# teensy-boom-jr.net
KiCad netlist of a schematic drawn in EAGLE
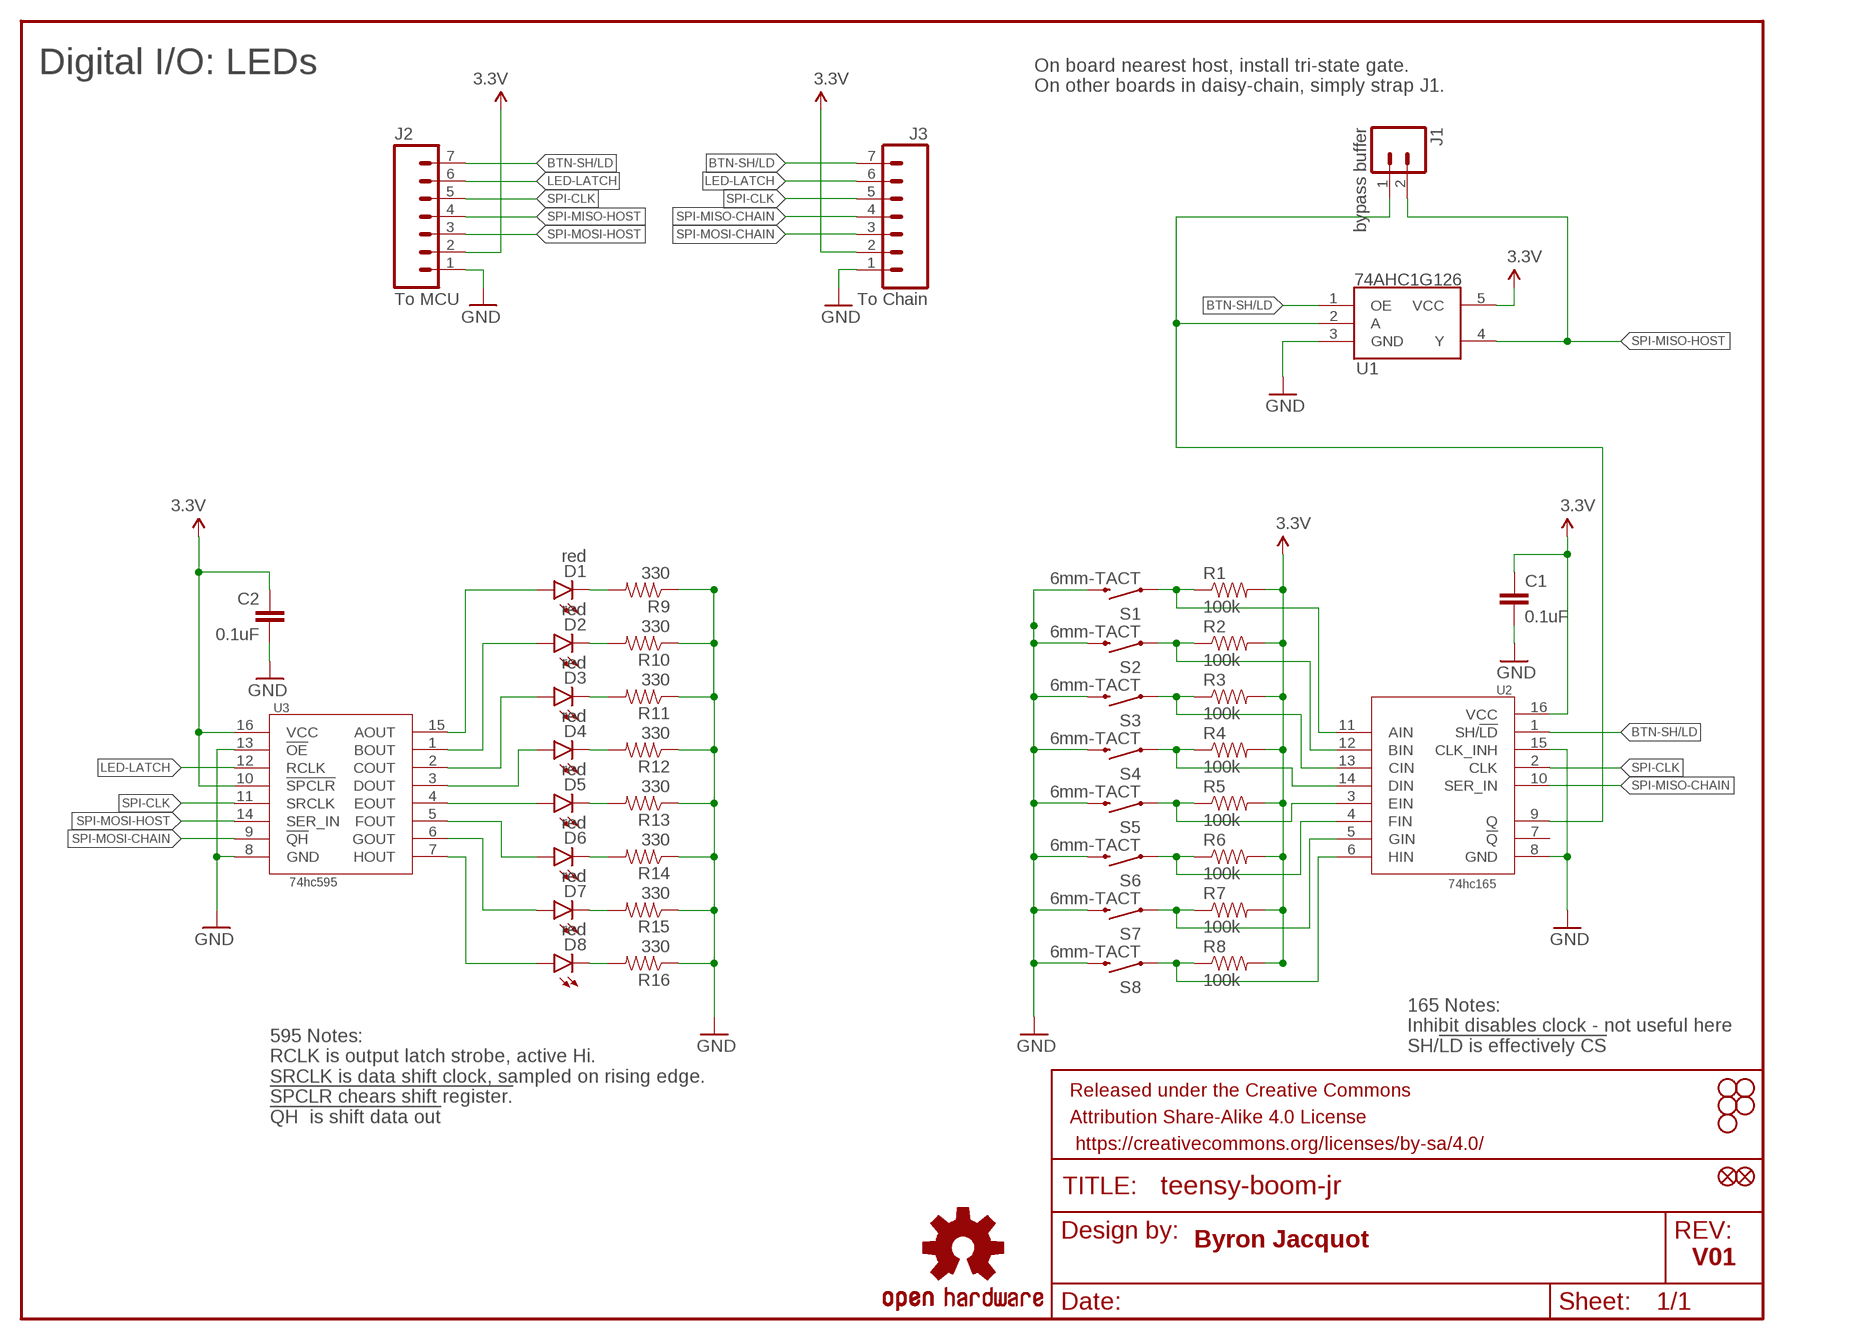
[diagram p0: schematic, sheet 1]

(export (version "E")
  (design (tool "Eeschema 10.0.6"))
  (components
    (comp (ref "C1")
      (value "0.1uF")
      (footprint "eagle-import:0603-CAP")
      (libsource (lib "eagle-import") (part "0.1UF-25V-5%(0603)"))
    )
    (comp (ref "C2")
      (value "0.1uF")
      (footprint "eagle-import:0603-CAP")
      (libsource (lib "eagle-import") (part "0.1UF-25V-5%(0603)"))
    )
    (comp (ref "D1")
      (value "red")
      (footprint "eagle-import:LED3MM-NS")
      (libsource (lib "eagle-import") (part "LED-3MM-NO_SILK"))
    )
    (comp (ref "D2")
      (value "red")
      (footprint "eagle-import:LED3MM-NS")
      (libsource (lib "eagle-import") (part "LED-3MM-NO_SILK"))
    )
    (comp (ref "D3")
      (value "red")
      (footprint "eagle-import:LED3MM-NS")
      (libsource (lib "eagle-import") (part "LED-3MM-NO_SILK"))
    )
    (comp (ref "D4")
      (value "red")
      (footprint "eagle-import:LED3MM-NS")
      (libsource (lib "eagle-import") (part "LED-3MM-NO_SILK"))
    )
    (comp (ref "D5")
      (value "red")
      (footprint "eagle-import:LED3MM-NS")
      (libsource (lib "eagle-import") (part "LED-3MM-NO_SILK"))
    )
    (comp (ref "D6")
      (value "red")
      (footprint "eagle-import:LED3MM-NS")
      (libsource (lib "eagle-import") (part "LED-3MM-NO_SILK"))
    )
    (comp (ref "D7")
      (value "red")
      (footprint "eagle-import:LED3MM-NS")
      (libsource (lib "eagle-import") (part "LED-3MM-NO_SILK"))
    )
    (comp (ref "D8")
      (value "red")
      (footprint "eagle-import:LED3MM-NS")
      (libsource (lib "eagle-import") (part "LED-3MM-NO_SILK"))
    )
    (comp (ref "FD1")
      (value "FIDUCIALUFIDUCIAL")
      (footprint "eagle-import:MICRO-FIDUCIAL")
      (libsource (lib "eagle-import") (part "FIDUCIALUFIDUCIAL"))
    )
    (comp (ref "FD2")
      (value "FIDUCIALUFIDUCIAL")
      (footprint "eagle-import:MICRO-FIDUCIAL")
      (libsource (lib "eagle-import") (part "FIDUCIALUFIDUCIAL"))
    )
    (comp (ref "FRAME1")
      (value "FRAME-LETTER")
      (footprint "eagle-import:CREATIVE_COMMONS")
      (libsource (lib "eagle-import") (part "FRAME-LETTER"))
    )
    (comp (ref "H1")
      (value "STAND-OFF")
      (footprint "eagle-import:STAND-OFF")
      (libsource (lib "eagle-import") (part "STAND-OFF"))
    )
    (comp (ref "H2")
      (value "STAND-OFF")
      (footprint "eagle-import:STAND-OFF")
      (libsource (lib "eagle-import") (part "STAND-OFF"))
    )
    (comp (ref "H3")
      (value "STAND-OFF")
      (footprint "eagle-import:STAND-OFF")
      (libsource (lib "eagle-import") (part "STAND-OFF"))
    )
    (comp (ref "H4")
      (value "STAND-OFF")
      (footprint "eagle-import:STAND-OFF")
      (libsource (lib "eagle-import") (part "STAND-OFF"))
    )
    (comp (ref "H5")
      (value "STAND-OFF")
      (footprint "eagle-import:STAND-OFF")
      (libsource (lib "eagle-import") (part "STAND-OFF"))
    )
    (comp (ref "J1")
      (value "bypass buffer")
      (footprint "eagle-import:1X02_NO_SILK")
      (libsource (lib "eagle-import") (part "M021X02_NO_SILK"))
    )
    (comp (ref "J2")
      (value "To MCU")
      (footprint "eagle-import:1X07_NO_SILK")
      (libsource (lib "eagle-import") (part "M07NO_SILK"))
    )
    (comp (ref "J3")
      (value "To Chain")
      (footprint "eagle-import:1X07_NO_SILK")
      (libsource (lib "eagle-import") (part "M07NO_SILK"))
    )
    (comp (ref "LOGO1")
      (value "OSHW-LOGOS")
      (footprint "eagle-import:OSHW-LOGO-S")
      (libsource (lib "eagle-import") (part "OSHW-LOGOS"))
    )
    (comp (ref "R1")
      (value "100k")
      (footprint "eagle-import:0805")
      (libsource (lib "eagle-import") (part "RESISTOR0805-RES"))
    )
    (comp (ref "R2")
      (value "100k")
      (footprint "eagle-import:0805")
      (libsource (lib "eagle-import") (part "RESISTOR0805-RES"))
    )
    (comp (ref "R3")
      (value "100k")
      (footprint "eagle-import:0805")
      (libsource (lib "eagle-import") (part "RESISTOR0805-RES"))
    )
    (comp (ref "R4")
      (value "100k")
      (footprint "eagle-import:0805")
      (libsource (lib "eagle-import") (part "RESISTOR0805-RES"))
    )
    (comp (ref "R5")
      (value "100k")
      (footprint "eagle-import:0805")
      (libsource (lib "eagle-import") (part "RESISTOR0805-RES"))
    )
    (comp (ref "R6")
      (value "100k")
      (footprint "eagle-import:0805")
      (libsource (lib "eagle-import") (part "RESISTOR0805-RES"))
    )
    (comp (ref "R7")
      (value "100k")
      (footprint "eagle-import:0805")
      (libsource (lib "eagle-import") (part "RESISTOR0805-RES"))
    )
    (comp (ref "R8")
      (value "100k")
      (footprint "eagle-import:0805")
      (libsource (lib "eagle-import") (part "RESISTOR0805-RES"))
    )
    (comp (ref "R9")
      (value "330")
      (footprint "eagle-import:0603-RES")
      (libsource (lib "eagle-import") (part "330OHM1/10W1%(0603)"))
    )
    (comp (ref "R10")
      (value "330")
      (footprint "eagle-import:0603-RES")
      (libsource (lib "eagle-import") (part "330OHM1/10W1%(0603)"))
    )
    (comp (ref "R11")
      (value "330")
      (footprint "eagle-import:0603-RES")
      (libsource (lib "eagle-import") (part "330OHM1/10W1%(0603)"))
    )
    (comp (ref "R12")
      (value "330")
      (footprint "eagle-import:0603-RES")
      (libsource (lib "eagle-import") (part "330OHM1/10W1%(0603)"))
    )
    (comp (ref "R13")
      (value "330")
      (footprint "eagle-import:0603-RES")
      (libsource (lib "eagle-import") (part "330OHM1/10W1%(0603)"))
    )
    (comp (ref "R14")
      (value "330")
      (footprint "eagle-import:0603-RES")
      (libsource (lib "eagle-import") (part "330OHM1/10W1%(0603)"))
    )
    (comp (ref "R15")
      (value "330")
      (footprint "eagle-import:0603-RES")
      (libsource (lib "eagle-import") (part "330OHM1/10W1%(0603)"))
    )
    (comp (ref "R16")
      (value "330")
      (footprint "eagle-import:0603-RES")
      (libsource (lib "eagle-import") (part "330OHM1/10W1%(0603)"))
    )
    (comp (ref "S1")
      (value "6mm-TACT")
      (footprint "eagle-import:TACTILE-PTH-12MM")
      (libsource (lib "eagle-import") (part "SWITCH-MOMENTARY-212MM"))
    )
    (comp (ref "S2")
      (value "6mm-TACT")
      (footprint "eagle-import:TACTILE-PTH-12MM")
      (libsource (lib "eagle-import") (part "SWITCH-MOMENTARY-212MM"))
    )
    (comp (ref "S3")
      (value "6mm-TACT")
      (footprint "eagle-import:TACTILE-PTH-12MM")
      (libsource (lib "eagle-import") (part "SWITCH-MOMENTARY-212MM"))
    )
    (comp (ref "S4")
      (value "6mm-TACT")
      (footprint "eagle-import:TACTILE-PTH-12MM")
      (libsource (lib "eagle-import") (part "SWITCH-MOMENTARY-212MM"))
    )
    (comp (ref "S5")
      (value "6mm-TACT")
      (footprint "eagle-import:TACTILE-PTH-12MM")
      (libsource (lib "eagle-import") (part "SWITCH-MOMENTARY-212MM"))
    )
    (comp (ref "S6")
      (value "6mm-TACT")
      (footprint "eagle-import:TACTILE-PTH-12MM")
      (libsource (lib "eagle-import") (part "SWITCH-MOMENTARY-212MM"))
    )
    (comp (ref "S7")
      (value "6mm-TACT")
      (footprint "eagle-import:TACTILE-PTH-12MM")
      (libsource (lib "eagle-import") (part "SWITCH-MOMENTARY-212MM"))
    )
    (comp (ref "S8")
      (value "6mm-TACT")
      (footprint "eagle-import:TACTILE-PTH-12MM")
      (libsource (lib "eagle-import") (part "SWITCH-MOMENTARY-212MM"))
    )
    (comp (ref "U1")
      (value "74AHC1G126")
      (footprint "eagle-import:SOT23-5")
      (libsource (lib "eagle-import") (part "74AHC1G126"))
    )
    (comp (ref "U2")
      (value "74hc165")
      (footprint "eagle-import:SO16")
      (libsource (lib "eagle-import") (part "74HC165"))
    )
    (comp (ref "U3")
      (value "74hc595")
      (footprint "eagle-import:SO16")
      (libsource (lib "eagle-import") (part "74HC595"))
    )
  )
  (nets
    (net (code "1") (name "3.3V") (class "Default")
      (node (ref "C1") (pin "1") (pinfunction "1_1") (pintype "passive"))
      (node (ref "C2") (pin "1") (pinfunction "1_1") (pintype "passive"))
      (node (ref "J2") (pin "2") (pinfunction "2_2") (pintype "passive"))
      (node (ref "J3") (pin "2") (pinfunction "2_2") (pintype "passive"))
      (node (ref "R1") (pin "2") (pinfunction "2_2") (pintype "passive"))
      (node (ref "R2") (pin "2") (pinfunction "2_2") (pintype "passive"))
      (node (ref "R3") (pin "2") (pinfunction "2_2") (pintype "passive"))
      (node (ref "R4") (pin "2") (pinfunction "2_2") (pintype "passive"))
      (node (ref "R5") (pin "2") (pinfunction "2_2") (pintype "passive"))
      (node (ref "R6") (pin "2") (pinfunction "2_2") (pintype "passive"))
      (node (ref "R7") (pin "2") (pinfunction "2_2") (pintype "passive"))
      (node (ref "R8") (pin "2") (pinfunction "2_2") (pintype "passive"))
      (node (ref "U1") (pin "5") (pinfunction "VCC_5") (pintype "bidirectional"))
      (node (ref "U2") (pin "16") (pinfunction "VCC_16") (pintype "bidirectional"))
      (node (ref "U3") (pin "10") (pinfunction "~{SPCLR}_10") (pintype "bidirectional"))
      (node (ref "U3") (pin "16") (pinfunction "VCC_16") (pintype "bidirectional"))
    )
    (net (code "2") (name "BTN-SH{slash}LD") (class "Default")
      (node (ref "J2") (pin "7") (pinfunction "7_7") (pintype "passive"))
      (node (ref "J3") (pin "7") (pinfunction "7_7") (pintype "passive"))
      (node (ref "U1") (pin "1") (pinfunction "OE_1") (pintype "bidirectional"))
      (node (ref "U2") (pin "1") (pinfunction "SH/~{LD}_1") (pintype "bidirectional"))
    )
    (net (code "3") (name "GND") (class "Default")
      (node (ref "C1") (pin "2") (pinfunction "2_2") (pintype "passive"))
      (node (ref "C2") (pin "2") (pinfunction "2_2") (pintype "passive"))
      (node (ref "J2") (pin "1") (pinfunction "1_1") (pintype "passive"))
      (node (ref "J3") (pin "1") (pinfunction "1_1") (pintype "passive"))
      (node (ref "R10") (pin "1") (pinfunction "1_1") (pintype "passive"))
      (node (ref "R11") (pin "1") (pinfunction "1_1") (pintype "passive"))
      (node (ref "R12") (pin "1") (pinfunction "1_1") (pintype "passive"))
      (node (ref "R13") (pin "1") (pinfunction "1_1") (pintype "passive"))
      (node (ref "R14") (pin "1") (pinfunction "1_1") (pintype "passive"))
      (node (ref "R15") (pin "1") (pinfunction "1_1") (pintype "passive"))
      (node (ref "R16") (pin "1") (pinfunction "1_1") (pintype "passive"))
      (node (ref "R9") (pin "1") (pinfunction "1_1") (pintype "passive"))
      (node (ref "S1") (pin "3") (pinfunction "2_3") (pintype "passive"))
      (node (ref "S2") (pin "3") (pinfunction "2_3") (pintype "passive"))
      (node (ref "S3") (pin "3") (pinfunction "2_3") (pintype "passive"))
      (node (ref "S4") (pin "3") (pinfunction "2_3") (pintype "passive"))
      (node (ref "S5") (pin "3") (pinfunction "2_3") (pintype "passive"))
      (node (ref "S6") (pin "3") (pinfunction "2_3") (pintype "passive"))
      (node (ref "S7") (pin "3") (pinfunction "2_3") (pintype "passive"))
      (node (ref "S8") (pin "3") (pinfunction "2_3") (pintype "passive"))
      (node (ref "U1") (pin "3") (pinfunction "GND_3") (pintype "bidirectional"))
      (node (ref "U2") (pin "15") (pinfunction "CLK_INH_15") (pintype "bidirectional"))
      (node (ref "U2") (pin "8") (pinfunction "GND_8") (pintype "bidirectional"))
      (node (ref "U3") (pin "13") (pinfunction "~{OE}_13") (pintype "bidirectional"))
      (node (ref "U3") (pin "8") (pinfunction "GND_8") (pintype "bidirectional"))
    )
    (net (code "4") (name "LED-LATCH") (class "Default")
      (node (ref "J2") (pin "6") (pinfunction "6_6") (pintype "passive"))
      (node (ref "J3") (pin "6") (pinfunction "6_6") (pintype "passive"))
      (node (ref "U3") (pin "12") (pinfunction "RCLK_12") (pintype "bidirectional"))
    )
    (net (code "5") (name "Net-(D1-C)") (class "Default")
      (node (ref "D1") (pin "K") (pinfunction "C_K") (pintype "passive"))
      (node (ref "R9") (pin "2") (pinfunction "2_2") (pintype "passive"))
    )
    (net (code "6") (name "Net-(D2-C)") (class "Default")
      (node (ref "D2") (pin "K") (pinfunction "C_K") (pintype "passive"))
      (node (ref "R10") (pin "2") (pinfunction "2_2") (pintype "passive"))
    )
    (net (code "7") (name "Net-(D3-C)") (class "Default")
      (node (ref "D3") (pin "K") (pinfunction "C_K") (pintype "passive"))
      (node (ref "R11") (pin "2") (pinfunction "2_2") (pintype "passive"))
    )
    (net (code "8") (name "Net-(D4-C)") (class "Default")
      (node (ref "D4") (pin "K") (pinfunction "C_K") (pintype "passive"))
      (node (ref "R12") (pin "2") (pinfunction "2_2") (pintype "passive"))
    )
    (net (code "9") (name "Net-(D5-C)") (class "Default")
      (node (ref "D5") (pin "K") (pinfunction "C_K") (pintype "passive"))
      (node (ref "R13") (pin "2") (pinfunction "2_2") (pintype "passive"))
    )
    (net (code "10") (name "Net-(D6-C)") (class "Default")
      (node (ref "D6") (pin "K") (pinfunction "C_K") (pintype "passive"))
      (node (ref "R14") (pin "2") (pinfunction "2_2") (pintype "passive"))
    )
    (net (code "11") (name "Net-(D7-C)") (class "Default")
      (node (ref "D7") (pin "K") (pinfunction "C_K") (pintype "passive"))
      (node (ref "R15") (pin "2") (pinfunction "2_2") (pintype "passive"))
    )
    (net (code "12") (name "Net-(D8-C)") (class "Default")
      (node (ref "D8") (pin "K") (pinfunction "C_K") (pintype "passive"))
      (node (ref "R16") (pin "2") (pinfunction "2_2") (pintype "passive"))
    )
    (net (code "13") (name "Net-(U1-A)") (class "Default")
      (node (ref "J1") (pin "1") (pinfunction "1_1") (pintype "passive"))
      (node (ref "U1") (pin "2") (pinfunction "A_2") (pintype "bidirectional"))
      (node (ref "U2") (pin "9") (pinfunction "Q_9") (pintype "bidirectional"))
    )
    (net (code "14") (name "Net-(U2-AIN)") (class "Default")
      (node (ref "R1") (pin "1") (pinfunction "1_1") (pintype "passive"))
      (node (ref "S1") (pin "1") (pinfunction "1_1") (pintype "passive"))
      (node (ref "U2") (pin "11") (pinfunction "AIN_11") (pintype "bidirectional"))
    )
    (net (code "15") (name "Net-(U2-BIN)") (class "Default")
      (node (ref "R2") (pin "1") (pinfunction "1_1") (pintype "passive"))
      (node (ref "S2") (pin "1") (pinfunction "1_1") (pintype "passive"))
      (node (ref "U2") (pin "12") (pinfunction "BIN_12") (pintype "bidirectional"))
    )
    (net (code "16") (name "Net-(U2-CIN)") (class "Default")
      (node (ref "R3") (pin "1") (pinfunction "1_1") (pintype "passive"))
      (node (ref "S3") (pin "1") (pinfunction "1_1") (pintype "passive"))
      (node (ref "U2") (pin "13") (pinfunction "CIN_13") (pintype "bidirectional"))
    )
    (net (code "17") (name "Net-(U2-DIN)") (class "Default")
      (node (ref "R4") (pin "1") (pinfunction "1_1") (pintype "passive"))
      (node (ref "S4") (pin "1") (pinfunction "1_1") (pintype "passive"))
      (node (ref "U2") (pin "14") (pinfunction "DIN_14") (pintype "bidirectional"))
    )
    (net (code "18") (name "Net-(U2-EIN)") (class "Default")
      (node (ref "R5") (pin "1") (pinfunction "1_1") (pintype "passive"))
      (node (ref "S5") (pin "1") (pinfunction "1_1") (pintype "passive"))
      (node (ref "U2") (pin "3") (pinfunction "EIN_3") (pintype "bidirectional"))
    )
    (net (code "19") (name "Net-(U2-FIN)") (class "Default")
      (node (ref "R6") (pin "1") (pinfunction "1_1") (pintype "passive"))
      (node (ref "S6") (pin "1") (pinfunction "1_1") (pintype "passive"))
      (node (ref "U2") (pin "4") (pinfunction "FIN_4") (pintype "bidirectional"))
    )
    (net (code "20") (name "Net-(U2-GIN)") (class "Default")
      (node (ref "R7") (pin "1") (pinfunction "1_1") (pintype "passive"))
      (node (ref "S7") (pin "1") (pinfunction "1_1") (pintype "passive"))
      (node (ref "U2") (pin "5") (pinfunction "GIN_5") (pintype "bidirectional"))
    )
    (net (code "21") (name "Net-(U2-HIN)") (class "Default")
      (node (ref "R8") (pin "1") (pinfunction "1_1") (pintype "passive"))
      (node (ref "S8") (pin "1") (pinfunction "1_1") (pintype "passive"))
      (node (ref "U2") (pin "6") (pinfunction "HIN_6") (pintype "bidirectional"))
    )
    (net (code "22") (name "Net-(U3-AOUT)") (class "Default")
      (node (ref "D1") (pin "A") (pinfunction "A_A") (pintype "passive"))
      (node (ref "U3") (pin "15") (pinfunction "AOUT_15") (pintype "bidirectional"))
    )
    (net (code "23") (name "Net-(U3-BOUT)") (class "Default")
      (node (ref "D2") (pin "A") (pinfunction "A_A") (pintype "passive"))
      (node (ref "U3") (pin "1") (pinfunction "BOUT_1") (pintype "bidirectional"))
    )
    (net (code "24") (name "Net-(U3-COUT)") (class "Default")
      (node (ref "D3") (pin "A") (pinfunction "A_A") (pintype "passive"))
      (node (ref "U3") (pin "2") (pinfunction "COUT_2") (pintype "bidirectional"))
    )
    (net (code "25") (name "Net-(U3-DOUT)") (class "Default")
      (node (ref "D4") (pin "A") (pinfunction "A_A") (pintype "passive"))
      (node (ref "U3") (pin "3") (pinfunction "DOUT_3") (pintype "bidirectional"))
    )
    (net (code "26") (name "Net-(U3-EOUT)") (class "Default")
      (node (ref "D5") (pin "A") (pinfunction "A_A") (pintype "passive"))
      (node (ref "U3") (pin "4") (pinfunction "EOUT_4") (pintype "bidirectional"))
    )
    (net (code "27") (name "Net-(U3-FOUT)") (class "Default")
      (node (ref "D6") (pin "A") (pinfunction "A_A") (pintype "passive"))
      (node (ref "U3") (pin "5") (pinfunction "FOUT_5") (pintype "bidirectional"))
    )
    (net (code "28") (name "Net-(U3-GOUT)") (class "Default")
      (node (ref "D7") (pin "A") (pinfunction "A_A") (pintype "passive"))
      (node (ref "U3") (pin "6") (pinfunction "GOUT_6") (pintype "bidirectional"))
    )
    (net (code "29") (name "Net-(U3-HOUT)") (class "Default")
      (node (ref "D8") (pin "A") (pinfunction "A_A") (pintype "passive"))
      (node (ref "U3") (pin "7") (pinfunction "HOUT_7") (pintype "bidirectional"))
    )
    (net (code "30") (name "SPI-CLK") (class "Default")
      (node (ref "J2") (pin "5") (pinfunction "5_5") (pintype "passive"))
      (node (ref "J3") (pin "5") (pinfunction "5_5") (pintype "passive"))
      (node (ref "U2") (pin "2") (pinfunction "CLK_2") (pintype "bidirectional"))
      (node (ref "U3") (pin "11") (pinfunction "SRCLK_11") (pintype "bidirectional"))
    )
    (net (code "31") (name "SPI-MISO-CHAIN") (class "Default")
      (node (ref "J3") (pin "4") (pinfunction "4_4") (pintype "passive"))
      (node (ref "U2") (pin "10") (pinfunction "SER_IN_10") (pintype "bidirectional"))
    )
    (net (code "32") (name "SPI-MISO-HOST") (class "Default")
      (node (ref "J1") (pin "2") (pinfunction "2_2") (pintype "passive"))
      (node (ref "J2") (pin "4") (pinfunction "4_4") (pintype "passive"))
      (node (ref "U1") (pin "4") (pinfunction "Y_4") (pintype "bidirectional"))
    )
    (net (code "33") (name "SPI-MOSI-CHAIN") (class "Default")
      (node (ref "J3") (pin "3") (pinfunction "3_3") (pintype "passive"))
      (node (ref "U3") (pin "9") (pinfunction "~{QH}_9") (pintype "bidirectional"))
    )
    (net (code "34") (name "SPI-MOSI-HOST") (class "Default")
      (node (ref "J2") (pin "3") (pinfunction "3_3") (pintype "passive"))
      (node (ref "U3") (pin "14") (pinfunction "SER_IN_14") (pintype "bidirectional"))
    )
    (net (code "35") (name "unconnected-(U2-~{Q}-Pad7)") (class "Default")
      (node (ref "U2") (pin "7") (pinfunction "~{Q}_7") (pintype "bidirectional"))
    )
  )
)
